# pmm.net
KiCad netlist of a schematic drawn in EAGLE
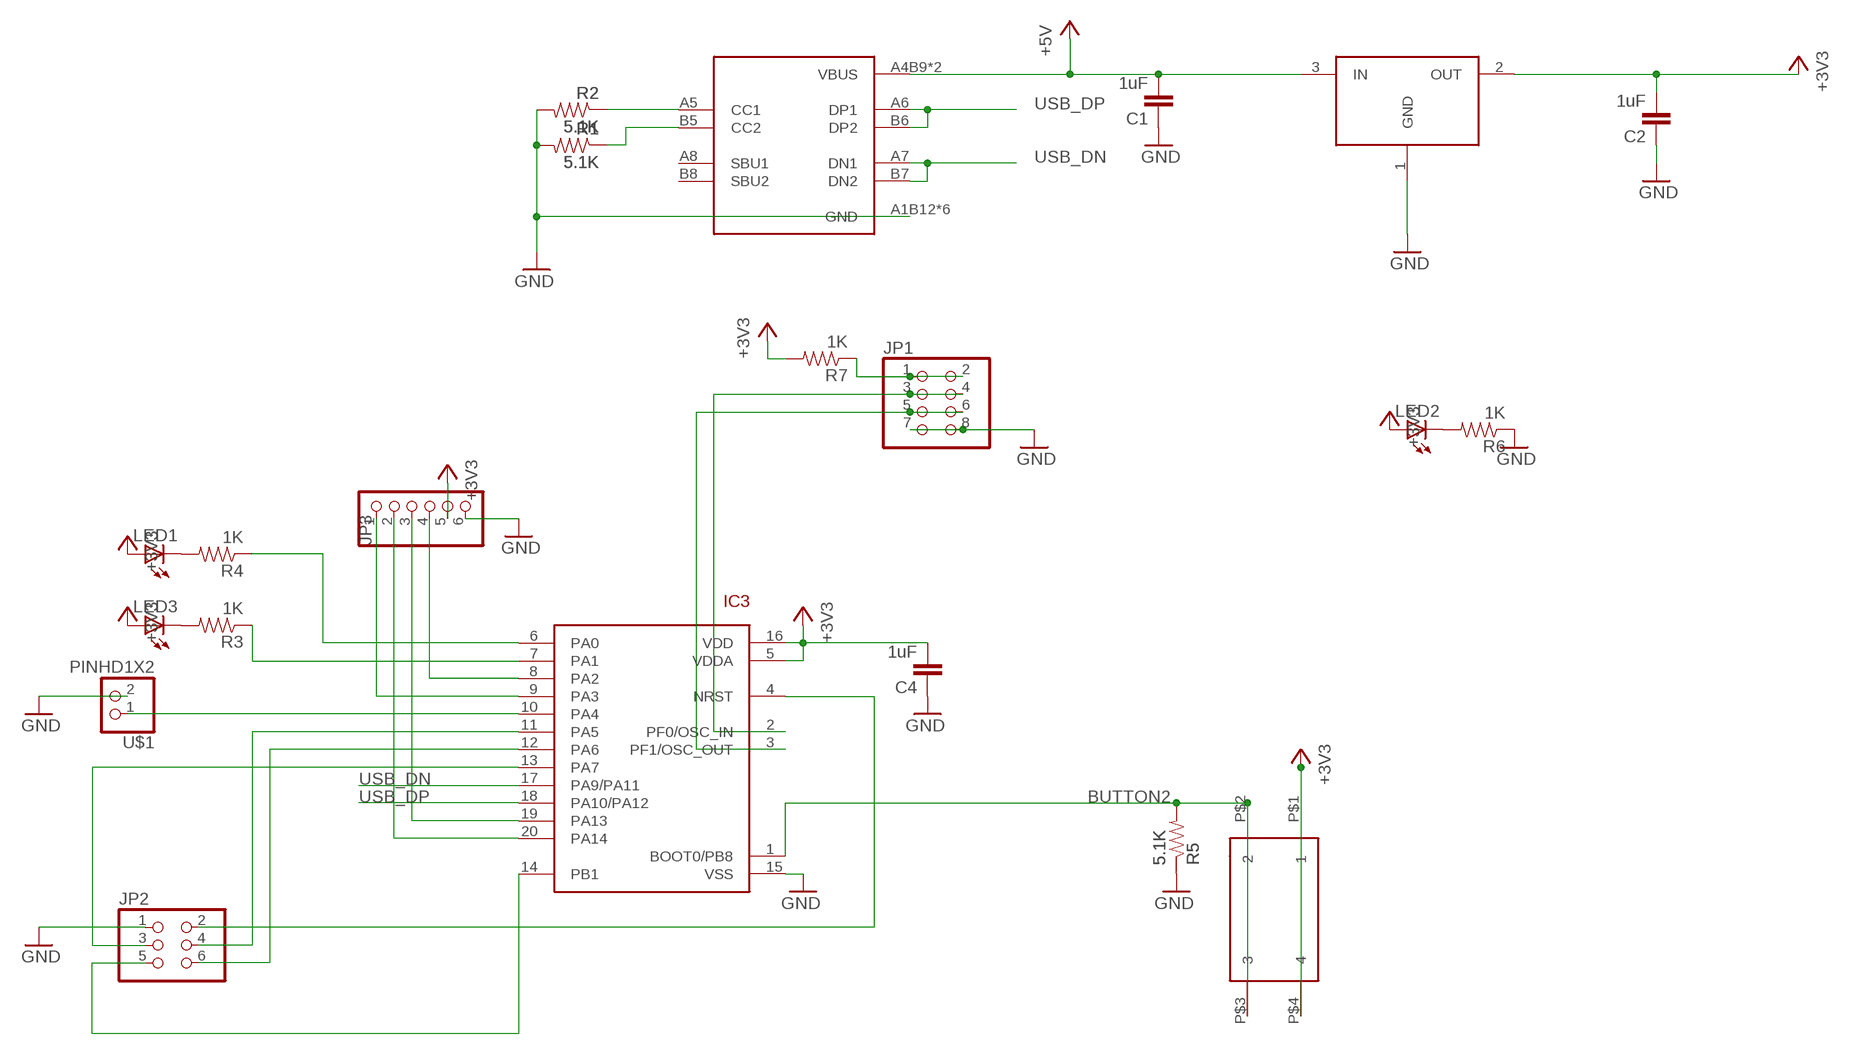
[diagram p0: schematic, sheet 1]

(export (version "E")
  (design (tool "Eeschema 10.0.6"))
  (components
    (comp (ref "C1")
      (value "1uF")
      (footprint "eagle-import:0805@1")
      (libsource (lib "eagle-import") (part "CAP0805"))
    )
    (comp (ref "C2")
      (value "1uF")
      (footprint "eagle-import:0805@1")
      (libsource (lib "eagle-import") (part "CAP0805"))
    )
    (comp (ref "C4")
      (value "1uF")
      (footprint "eagle-import:0805@1")
      (libsource (lib "eagle-import") (part "CAP0805"))
    )
    (comp (ref "IC3")
      (value "STM32F042F4")
      (footprint "eagle-import:TSSOP20")
      (libsource (lib "eagle-import") (part "STM32F042F4"))
    )
    (comp (ref "JP1")
      (value "PINHEAD_PINHD-2X4")
      (footprint "eagle-import:PINHEAD_2X04")
      (libsource (lib "eagle-import") (part "PINHEAD_PINHD-2X4"))
    )
    (comp (ref "JP2")
      (value "PINHD-2X3")
      (footprint "eagle-import:2X03")
      (libsource (lib "eagle-import") (part "PINHD-2X3"))
    )
    (comp (ref "JP3")
      (value "PINHD-1X6")
      (footprint "eagle-import:1X06")
      (libsource (lib "eagle-import") (part "PINHD-1X6"))
    )
    (comp (ref "LED1")
      (value "LEDCHIP-LED0805")
      (footprint "eagle-import:CHIP-LED0805")
      (libsource (lib "eagle-import") (part "LEDCHIP-LED0805"))
    )
    (comp (ref "LED2")
      (value "LEDCHIP-LED0805")
      (footprint "eagle-import:CHIP-LED0805")
      (libsource (lib "eagle-import") (part "LEDCHIP-LED0805"))
    )
    (comp (ref "LED3")
      (value "LEDCHIP-LED0805")
      (footprint "eagle-import:CHIP-LED0805")
      (libsource (lib "eagle-import") (part "LEDCHIP-LED0805"))
    )
    (comp (ref "R1")
      (value "5.1K")
      (footprint "eagle-import:0805")
      (libsource (lib "eagle-import") (part "joyAnalog_RESISTOR0805-RES"))
    )
    (comp (ref "R2")
      (value "5.1K")
      (footprint "eagle-import:0805")
      (libsource (lib "eagle-import") (part "joyAnalog_RESISTOR0805-RES"))
    )
    (comp (ref "R3")
      (value "1K")
      (footprint "eagle-import:0805")
      (libsource (lib "eagle-import") (part "RESISTOR0805-RES"))
    )
    (comp (ref "R4")
      (value "1K")
      (footprint "eagle-import:0805")
      (libsource (lib "eagle-import") (part "RESISTOR0805-RES"))
    )
    (comp (ref "R5")
      (value "5.1K")
      (footprint "eagle-import:0805")
      (libsource (lib "eagle-import") (part "joyAnalog_RESISTOR0805-RES"))
    )
    (comp (ref "R6")
      (value "1K")
      (footprint "eagle-import:0805")
      (libsource (lib "eagle-import") (part "RESISTOR0805-RES"))
    )
    (comp (ref "R7")
      (value "1K")
      (footprint "eagle-import:0805")
      (libsource (lib "eagle-import") (part "RESISTOR0805-RES"))
    )
    (comp (ref "SW4")
      (value "324_SW")
      (footprint "eagle-import:342_SWICH_FOOT")
      (libsource (lib "eagle-import") (part "324_SW"))
    )
    (comp (ref "U$1")
      (value "PINHD1X2")
      (footprint "eagle-import:1X02")
      (libsource (lib "eagle-import") (part "PINHD1X2"))
    )
    (comp (ref "U2")
      (value "USBC_16P")
      (footprint "eagle-import:USBC_16P_FOOT")
      (libsource (lib "eagle-import") (part "USBC_16P"))
    )
    (comp (ref "U4")
      (value "XC6206_DEV")
      (footprint "eagle-import:SOT23R_INFINEON")
      (libsource (lib "eagle-import") (part "XC6206_DEV"))
    )
  )
  (nets
    (net (code "1") (name "+3V3") (class "Default")
      (node (ref "C2") (pin "2") (pinfunction "2_2") (pintype "passive"))
      (node (ref "C4") (pin "2") (pinfunction "2_2") (pintype "passive"))
      (node (ref "IC3") (pin "16") (pinfunction "VDD_16") (pintype "bidirectional"))
      (node (ref "IC3") (pin "5") (pinfunction "VDDA_5") (pintype "bidirectional"))
      (node (ref "JP3") (pin "5") (pinfunction "5_5") (pintype "passive"))
      (node (ref "LED1") (pin "A") (pinfunction "A_A") (pintype "passive"))
      (node (ref "LED2") (pin "A") (pinfunction "A_A") (pintype "passive"))
      (node (ref "LED3") (pin "A") (pinfunction "A_A") (pintype "passive"))
      (node (ref "R7") (pin "2") (pinfunction "2_2") (pintype "passive"))
      (node (ref "SW4") (pin "P$1") (pinfunction "1_P$1") (pintype "bidirectional"))
      (node (ref "SW4") (pin "P$4") (pinfunction "4_P$4") (pintype "bidirectional"))
      (node (ref "U4") (pin "2") (pinfunction "OUT_2") (pintype "bidirectional"))
    )
    (net (code "2") (name "+5V") (class "Default")
      (node (ref "C1") (pin "2") (pinfunction "2_2") (pintype "passive"))
      (node (ref "U2") (pin "A4B9") (pinfunction "VBUS_A4B9") (pintype "bidirectional"))
      (node (ref "U2") (pin "B4A9") (pinfunction "VBUS_B4A9") (pintype "bidirectional"))
      (node (ref "U4") (pin "3") (pinfunction "IN_3") (pintype "bidirectional"))
    )
    (net (code "3") (name "/BUTTON2") (class "Default")
      (node (ref "IC3") (pin "1") (pinfunction "BOOT0/PB8_1") (pintype "bidirectional"))
      (node (ref "R5") (pin "2") (pinfunction "2_2") (pintype "passive"))
      (node (ref "SW4") (pin "P$2") (pinfunction "2_P$2") (pintype "bidirectional"))
      (node (ref "SW4") (pin "P$3") (pinfunction "3_P$3") (pintype "bidirectional"))
    )
    (net (code "4") (name "/USB_DN") (class "Default")
      (node (ref "IC3") (pin "17") (pinfunction "PA9/PA11_17") (pintype "bidirectional"))
      (node (ref "U2") (pin "A7") (pinfunction "DN1_A7") (pintype "bidirectional"))
      (node (ref "U2") (pin "B7") (pinfunction "DN2_B7") (pintype "bidirectional"))
    )
    (net (code "5") (name "/USB_DP") (class "Default")
      (node (ref "IC3") (pin "18") (pinfunction "PA10/PA12_18") (pintype "bidirectional"))
      (node (ref "U2") (pin "A6") (pinfunction "DP1_A6") (pintype "bidirectional"))
      (node (ref "U2") (pin "B6") (pinfunction "DP2_B6") (pintype "bidirectional"))
    )
    (net (code "6") (name "GND") (class "Default")
      (node (ref "C1") (pin "1") (pinfunction "1_1") (pintype "passive"))
      (node (ref "C2") (pin "1") (pinfunction "1_1") (pintype "passive"))
      (node (ref "C4") (pin "1") (pinfunction "1_1") (pintype "passive"))
      (node (ref "IC3") (pin "15") (pinfunction "VSS_15") (pintype "bidirectional"))
      (node (ref "JP1") (pin "7") (pinfunction "7_7") (pintype "passive"))
      (node (ref "JP1") (pin "8") (pinfunction "8_8") (pintype "passive"))
      (node (ref "JP2") (pin "1") (pinfunction "1_1") (pintype "passive"))
      (node (ref "JP3") (pin "6") (pinfunction "6_6") (pintype "passive"))
      (node (ref "R1") (pin "2") (pinfunction "2_2") (pintype "passive"))
      (node (ref "R2") (pin "2") (pinfunction "2_2") (pintype "passive"))
      (node (ref "R5") (pin "1") (pinfunction "1_1") (pintype "passive"))
      (node (ref "R6") (pin "1") (pinfunction "1_1") (pintype "passive"))
      (node (ref "U$1") (pin "2") (pinfunction "2_2") (pintype "passive"))
      (node (ref "U2") (pin "A1B12") (pinfunction "GND_A1B12") (pintype "bidirectional"))
      (node (ref "U2") (pin "B11A12") (pinfunction "GND_B11A12") (pintype "bidirectional"))
      (node (ref "U2") (pin "P$13") (pinfunction "GND_P$13") (pintype "bidirectional"))
      (node (ref "U2") (pin "P$14") (pinfunction "GND_P$14") (pintype "bidirectional"))
      (node (ref "U2") (pin "P$15") (pinfunction "GND_P$15") (pintype "bidirectional"))
      (node (ref "U2") (pin "P$16") (pinfunction "GND_P$16") (pintype "bidirectional"))
      (node (ref "U4") (pin "1") (pinfunction "GND_1") (pintype "bidirectional"))
    )
    (net (code "7") (name "Net-(IC3-NRST)") (class "Default")
      (node (ref "IC3") (pin "4") (pinfunction "NRST_4") (pintype "bidirectional"))
      (node (ref "JP2") (pin "2") (pinfunction "2_2") (pintype "passive"))
    )
    (net (code "8") (name "Net-(IC3-PA0)") (class "Default")
      (node (ref "IC3") (pin "6") (pinfunction "PA0_6") (pintype "bidirectional"))
      (node (ref "R4") (pin "1") (pinfunction "1_1") (pintype "passive"))
    )
    (net (code "9") (name "Net-(IC3-PA1)") (class "Default")
      (node (ref "IC3") (pin "7") (pinfunction "PA1_7") (pintype "bidirectional"))
      (node (ref "R3") (pin "1") (pinfunction "1_1") (pintype "passive"))
    )
    (net (code "10") (name "Net-(IC3-PA2)") (class "Default")
      (node (ref "IC3") (pin "8") (pinfunction "PA2_8") (pintype "bidirectional"))
      (node (ref "JP3") (pin "4") (pinfunction "4_4") (pintype "passive"))
    )
    (net (code "11") (name "Net-(IC3-PA3)") (class "Default")
      (node (ref "IC3") (pin "9") (pinfunction "PA3_9") (pintype "bidirectional"))
      (node (ref "JP3") (pin "1") (pinfunction "1_1") (pintype "passive"))
    )
    (net (code "12") (name "Net-(IC3-PA4)") (class "Default")
      (node (ref "IC3") (pin "10") (pinfunction "PA4_10") (pintype "bidirectional"))
      (node (ref "U$1") (pin "1") (pinfunction "1_1") (pintype "passive"))
    )
    (net (code "13") (name "Net-(IC3-PA5)") (class "Default")
      (node (ref "IC3") (pin "11") (pinfunction "PA5_11") (pintype "bidirectional"))
      (node (ref "JP2") (pin "4") (pinfunction "4_4") (pintype "passive"))
    )
    (net (code "14") (name "Net-(IC3-PA6)") (class "Default")
      (node (ref "IC3") (pin "12") (pinfunction "PA6_12") (pintype "bidirectional"))
      (node (ref "JP2") (pin "6") (pinfunction "6_6") (pintype "passive"))
    )
    (net (code "15") (name "Net-(IC3-PA7)") (class "Default")
      (node (ref "IC3") (pin "13") (pinfunction "PA7_13") (pintype "bidirectional"))
      (node (ref "JP2") (pin "3") (pinfunction "3_3") (pintype "passive"))
    )
    (net (code "16") (name "Net-(IC3-PA13)") (class "Default")
      (node (ref "IC3") (pin "19") (pinfunction "PA13_19") (pintype "bidirectional"))
      (node (ref "JP3") (pin "3") (pinfunction "3_3") (pintype "passive"))
    )
    (net (code "17") (name "Net-(IC3-PA14)") (class "Default")
      (node (ref "IC3") (pin "20") (pinfunction "PA14_20") (pintype "bidirectional"))
      (node (ref "JP3") (pin "2") (pinfunction "2_2") (pintype "passive"))
    )
    (net (code "18") (name "Net-(IC3-PB1)") (class "Default")
      (node (ref "IC3") (pin "14") (pinfunction "PB1_14") (pintype "bidirectional"))
      (node (ref "JP2") (pin "5") (pinfunction "5_5") (pintype "passive"))
    )
    (net (code "19") (name "Net-(IC3-PF0{slash}OSC_IN)") (class "Default")
      (node (ref "IC3") (pin "2") (pinfunction "PF0/OSC_IN_2") (pintype "bidirectional"))
      (node (ref "JP1") (pin "3") (pinfunction "3_3") (pintype "passive"))
      (node (ref "JP1") (pin "4") (pinfunction "4_4") (pintype "passive"))
    )
    (net (code "20") (name "Net-(IC3-PF1{slash}OSC_OUT)") (class "Default")
      (node (ref "IC3") (pin "3") (pinfunction "PF1/OSC_OUT_3") (pintype "bidirectional"))
      (node (ref "JP1") (pin "5") (pinfunction "5_5") (pintype "passive"))
      (node (ref "JP1") (pin "6") (pinfunction "6_6") (pintype "passive"))
    )
    (net (code "21") (name "Net-(JP1-Pad1)") (class "Default")
      (node (ref "JP1") (pin "1") (pinfunction "1_1") (pintype "passive"))
      (node (ref "JP1") (pin "2") (pinfunction "2_2") (pintype "passive"))
      (node (ref "R7") (pin "1") (pinfunction "1_1") (pintype "passive"))
    )
    (net (code "22") (name "Net-(LED1-PadC)") (class "Default")
      (node (ref "LED1") (pin "C") (pinfunction "C_C") (pintype "passive"))
      (node (ref "R4") (pin "2") (pinfunction "2_2") (pintype "passive"))
    )
    (net (code "23") (name "Net-(LED2-PadC)") (class "Default")
      (node (ref "LED2") (pin "C") (pinfunction "C_C") (pintype "passive"))
      (node (ref "R6") (pin "2") (pinfunction "2_2") (pintype "passive"))
    )
    (net (code "24") (name "Net-(LED3-PadC)") (class "Default")
      (node (ref "LED3") (pin "C") (pinfunction "C_C") (pintype "passive"))
      (node (ref "R3") (pin "2") (pinfunction "2_2") (pintype "passive"))
    )
    (net (code "25") (name "Net-(U2-CC1)") (class "Default")
      (node (ref "R2") (pin "1") (pinfunction "1_1") (pintype "passive"))
      (node (ref "U2") (pin "A5") (pinfunction "CC1_A5") (pintype "bidirectional"))
    )
    (net (code "26") (name "Net-(U2-CC2)") (class "Default")
      (node (ref "R1") (pin "1") (pinfunction "1_1") (pintype "passive"))
      (node (ref "U2") (pin "B5") (pinfunction "CC2_B5") (pintype "bidirectional"))
    )
    (net (code "27") (name "unconnected-(U2-SBU1-PadA8)") (class "Default")
      (node (ref "U2") (pin "A8") (pinfunction "SBU1_A8") (pintype "bidirectional"))
    )
    (net (code "28") (name "unconnected-(U2-SBU2-PadB8)") (class "Default")
      (node (ref "U2") (pin "B8") (pinfunction "SBU2_B8") (pintype "bidirectional"))
    )
  )
)
